# WIO_E5.net
KiCad netlist of a schematic drawn in Altium Designer
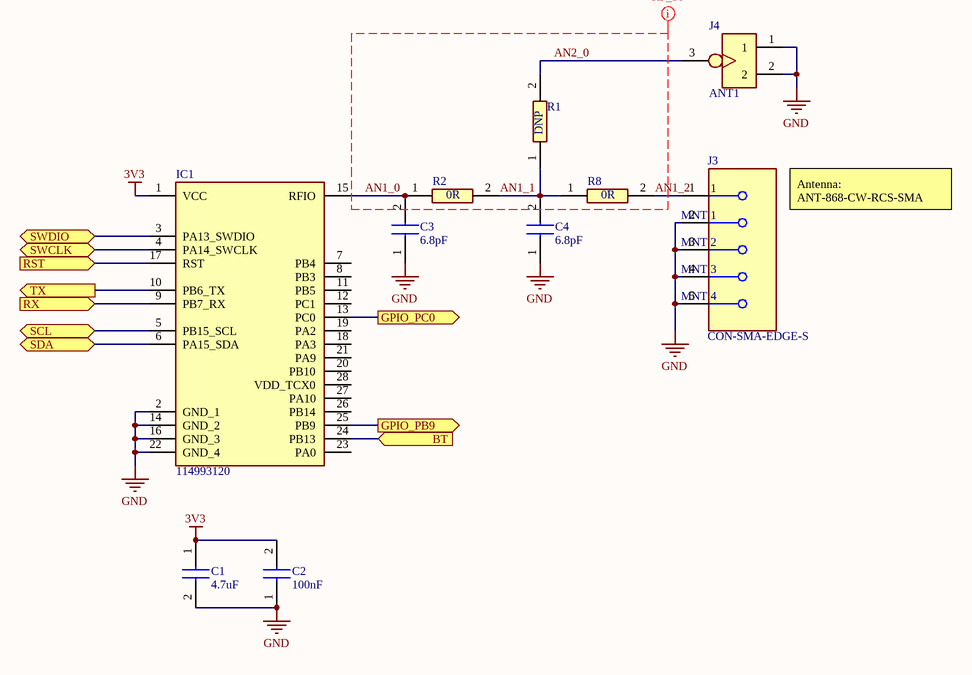
[diagram p0: WIO_E5.SchDoc]

(export (version "E")
  (design (tool "Eeschema 10.0.6"))
  (components
    (comp (ref "C1")
      (value "4.7uF")
      (footprint "SamacSys:CAPC1608X90N")
      (description "Capacitor")
      (fields
        (field (name "MANUFACTURER_PART_NUMBER") "GRM188R61E475KE11J")
        (field (name "MOUSER PART NUMBER") "81-GRM188R61E475KE1J")
      )
      (libsource (lib "*") (part "GRM188R61E475KE11J"))
    )
    (comp (ref "C2")
      (value "100nF")
      (footprint "SamacSys:CAPC1005X70N")
      (description "Capacitor")
      (fields
        (field (name "MANUFACTURER_PART_NUMBER") "GRM155R61A104KA01D")
        (field (name "MOUSER PART NUMBER") "81-GRM155R61A104KA01")
      )
      (libsource (lib "*") (part "GRM155R61A104KA01D"))
    )
    (comp (ref "C3")
      (value "6.8pF")
      (footprint "SamacSys:GCM155")
      (description "Capacitor")
      (fields
        (field (name "MANUFACTURER_PART_NUMBER") "GCM1555C1H6R8BA16J")
        (field (name "MOUSER PART NUMBER") "81-GCM1555C1H6R8BA6J")
      )
      (libsource (lib "*") (part "GCM1555C1H6R8BA16J"))
    )
    (comp (ref "C4")
      (value "6.8pF")
      (footprint "SamacSys:GCM155")
      (description "Capacitor")
      (fields
        (field (name "MANUFACTURER_PART_NUMBER") "GCM1555C1H6R8BA16J")
        (field (name "MOUSER PART NUMBER") "81-GCM1555C1H6R8BA6J")
      )
      (libsource (lib "*") (part "GCM1555C1H6R8BA16J"))
    )
    (comp (ref "IC1")
      (value "114993120")
      (footprint "SamacSys:114993120")
      (description "Integrated Circuit")
      (fields (field (name "MOUSER PART NUMBER") "713-114993120"))
      (libsource (lib "SamacSys") (part "114993120"))
    )
    (comp (ref "J3")
      (value "CON-SMA-EDGE-S")
      (footprint "FP-CON-SMA-EDGE-S-MFG")
      (description "CONN SMA JACK STR EDGE MNT")
      (fields
        (field (name "OCTOPART") "https://octopart.com/con-sma-edge-s-rf+solutions-70967450")
        (field (name "MANUFACTURER") "RF Solutions Ltd.")
      )
      (libsource (lib "Altium Content Vault") (part "a163d97a771fcdd2fd1f1a9264c171f"))
    )
    (comp (ref "J4")
      (value "ANT1")
      (footprint "SamacSys:RECE.20279.001E.01")
      (description "Connector")
      (fields (field (name "MANUFACTURER_PART_NUMBER") "RECE-20279-001E-01"))
      (libsource (lib "SamacSys") (part "RECE-20279-001E-01"))
    )
    (comp (ref "R1")
      (value "DNP")
      (footprint "SamacSys:RESC1005X40N")
      (description "Resistor")
      (fields
        (field (name "MANUFACTURER_PART_NUMBER") "RCA04020000ZSED")
        (field (name "MOUSER PART NUMBER") "71-RCA04020000ZSED")
      )
      (libsource (lib "") (part "RCA04020000ZSED_1"))
    )
    (comp (ref "R2")
      (value "0R")
      (footprint "SamacSys:RESC1005X40N")
      (description "Resistor")
      (fields
        (field (name "MANUFACTURER_PART_NUMBER") "RCA04020000ZSED")
        (field (name "MOUSER PART NUMBER") "71-RCA04020000ZSED")
      )
      (libsource (lib "SamacSys") (part "RCA04020000ZSED"))
    )
    (comp (ref "R8")
      (value "0R")
      (footprint "SamacSys:RESC1005X40N")
      (description "Resistor")
      (fields
        (field (name "MANUFACTURER_PART_NUMBER") "RCA04020000ZSED")
        (field (name "MOUSER PART NUMBER") "71-RCA04020000ZSED")
      )
      (libsource (lib "SamacSys") (part "RCA04020000ZSED"))
    )
  )
  (nets
    (net (code "1") (name "/AN1_0") (class "Default")
      (node (ref "C3") (pin "2") (pinfunction "2_2") (pintype "passive"))
      (node (ref "IC1") (pin "15") (pinfunction "RFIO_15") (pintype "passive"))
      (node (ref "R2") (pin "1") (pinfunction "1_1") (pintype "passive"))
    )
    (net (code "2") (name "/AN1_1") (class "Default")
      (node (ref "C4") (pin "2") (pinfunction "2_2") (pintype "passive"))
      (node (ref "R1") (pin "1") (pinfunction "1_1") (pintype "passive"))
      (node (ref "R2") (pin "2") (pinfunction "2_2") (pintype "passive"))
      (node (ref "R8") (pin "1") (pinfunction "1_1") (pintype "passive"))
    )
    (net (code "3") (name "/AN1_2") (class "Default")
      (node (ref "J3") (pin "1") (pinfunction "1_1") (pintype "passive"))
      (node (ref "R8") (pin "2") (pinfunction "2_2") (pintype "passive"))
    )
    (net (code "4") (name "/AN2_0") (class "Default")
      (node (ref "J4") (pin "3") (pinfunction "3_3") (pintype "passive"))
      (node (ref "R1") (pin "2") (pinfunction "2_2") (pintype "passive"))
    )
    (net (code "5") (name "/BT") (class "Default")
      (node (ref "IC1") (pin "24") (pinfunction "PB13_24") (pintype "passive"))
    )
    (net (code "6") (name "/GPIO_PB9") (class "Default")
      (node (ref "IC1") (pin "25") (pinfunction "PB9_25") (pintype "passive"))
    )
    (net (code "7") (name "/GPIO_PC0") (class "Default")
      (node (ref "IC1") (pin "13") (pinfunction "PC0_13") (pintype "passive"))
    )
    (net (code "8") (name "/RST") (class "Default")
      (node (ref "IC1") (pin "17") (pinfunction "RST_17") (pintype "passive"))
    )
    (net (code "9") (name "/RX") (class "Default")
      (node (ref "IC1") (pin "9") (pinfunction "PB7_RX_9") (pintype "passive"))
    )
    (net (code "10") (name "/SCL") (class "Default")
      (node (ref "IC1") (pin "5") (pinfunction "PB15_SCL_5") (pintype "passive"))
    )
    (net (code "11") (name "/SDA") (class "Default")
      (node (ref "IC1") (pin "6") (pinfunction "PA15_SDA_6") (pintype "passive"))
    )
    (net (code "12") (name "/SWCLK") (class "Default")
      (node (ref "IC1") (pin "4") (pinfunction "PA14_SWCLK_4") (pintype "passive"))
    )
    (net (code "13") (name "/SWDIO") (class "Default")
      (node (ref "IC1") (pin "3") (pinfunction "PA13_SWDIO_3") (pintype "passive"))
    )
    (net (code "14") (name "/TX") (class "Default")
      (node (ref "IC1") (pin "10") (pinfunction "PB6_TX_10") (pintype "passive"))
    )
    (net (code "15") (name "3V3") (class "Default")
      (node (ref "C1") (pin "1") (pinfunction "1_1") (pintype "passive"))
      (node (ref "C2") (pin "2") (pinfunction "2_2") (pintype "passive"))
      (node (ref "IC1") (pin "1") (pinfunction "VCC_1") (pintype "passive"))
    )
    (net (code "16") (name "GND") (class "Default")
      (node (ref "C1") (pin "2") (pinfunction "2_2") (pintype "passive"))
      (node (ref "C2") (pin "1") (pinfunction "1_1") (pintype "passive"))
      (node (ref "C3") (pin "1") (pinfunction "1_1") (pintype "passive"))
      (node (ref "C4") (pin "1") (pinfunction "1_1") (pintype "passive"))
      (node (ref "IC1") (pin "14") (pinfunction "GND_2_14") (pintype "passive"))
      (node (ref "IC1") (pin "16") (pinfunction "GND_3_16") (pintype "passive"))
      (node (ref "IC1") (pin "2") (pinfunction "GND_1_2") (pintype "passive"))
      (node (ref "IC1") (pin "22") (pinfunction "GND_4_22") (pintype "passive"))
      (node (ref "J3") (pin "2") (pinfunction "MNT_1_2") (pintype "passive"))
      (node (ref "J3") (pin "3") (pinfunction "MNT_2_3") (pintype "passive"))
      (node (ref "J3") (pin "4") (pinfunction "MNT_3_4") (pintype "passive"))
      (node (ref "J3") (pin "5") (pinfunction "MNT_4_5") (pintype "passive"))
      (node (ref "J4") (pin "1") (pinfunction "1_1") (pintype "passive"))
      (node (ref "J4") (pin "2") (pinfunction "2_2") (pintype "passive"))
    )
    (net (code "17") (name "unconnected-(IC1-PA0-Pad23)") (class "Default")
      (node (ref "IC1") (pin "23") (pinfunction "PA0_23") (pintype "passive"))
    )
    (net (code "18") (name "unconnected-(IC1-PA2-Pad19)") (class "Default")
      (node (ref "IC1") (pin "19") (pinfunction "PA2_19") (pintype "passive"))
    )
    (net (code "19") (name "unconnected-(IC1-PA3-Pad18)") (class "Default")
      (node (ref "IC1") (pin "18") (pinfunction "PA3_18") (pintype "passive"))
    )
    (net (code "20") (name "unconnected-(IC1-PA9-Pad21)") (class "Default")
      (node (ref "IC1") (pin "21") (pinfunction "PA9_21") (pintype "passive"))
    )
    (net (code "21") (name "unconnected-(IC1-PA10-Pad27)") (class "Default")
      (node (ref "IC1") (pin "27") (pinfunction "PA10_27") (pintype "passive"))
    )
    (net (code "22") (name "unconnected-(IC1-PB3-Pad8)") (class "Default")
      (node (ref "IC1") (pin "8") (pinfunction "PB3_8") (pintype "passive"))
    )
    (net (code "23") (name "unconnected-(IC1-PB4-Pad7)") (class "Default")
      (node (ref "IC1") (pin "7") (pinfunction "PB4_7") (pintype "passive"))
    )
    (net (code "24") (name "unconnected-(IC1-PB5-Pad11)") (class "Default")
      (node (ref "IC1") (pin "11") (pinfunction "PB5_11") (pintype "passive"))
    )
    (net (code "25") (name "unconnected-(IC1-PB10-Pad20)") (class "Default")
      (node (ref "IC1") (pin "20") (pinfunction "PB10_20") (pintype "passive"))
    )
    (net (code "26") (name "unconnected-(IC1-PB14-Pad26)") (class "Default")
      (node (ref "IC1") (pin "26") (pinfunction "PB14_26") (pintype "passive"))
    )
    (net (code "27") (name "unconnected-(IC1-PC1-Pad12)") (class "Default")
      (node (ref "IC1") (pin "12") (pinfunction "PC1_12") (pintype "passive"))
    )
    (net (code "28") (name "unconnected-(IC1-VDD_TCX0-Pad28)") (class "Default")
      (node (ref "IC1") (pin "28") (pinfunction "VDD_TCX0_28") (pintype "passive"))
    )
  )
)
